# bcdwatch.net
KiCad netlist of a schematic drawn in EAGLE
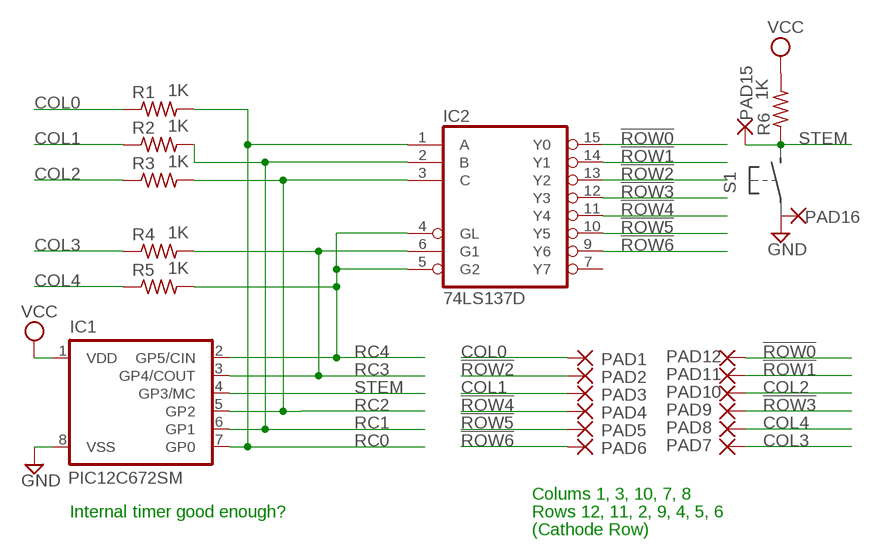
[diagram p0: schematic, sheet 1]

(export (version "E")
  (design (tool "Eeschema 10.0.6"))
  (components
    (comp (ref "IC1")
      (value "PIC12C672SM")
      (footprint "eagle-import:SO-08M")
      (fields (field (name "MF") "MICROCHIP") (field (name "MPN") "PIC12C672-04/SM"))
      (libsource (lib "eagle-import") (part "PIC12C?SM672"))
    )
    (comp (ref "IC2")
      (value "74LS137D")
      (footprint "eagle-import:SO16")
      (libsource (lib "eagle-import") (part "74137DLS"))
    )
    (comp (ref "PAD1")
      (value "SMD2")
      (footprint "eagle-import:SMD1,27-2,54")
      (libsource (lib "eagle-import") (part "SMD2"))
    )
    (comp (ref "PAD2")
      (value "SMD2")
      (footprint "eagle-import:SMD1,27-2,54")
      (libsource (lib "eagle-import") (part "SMD2"))
    )
    (comp (ref "PAD3")
      (value "SMD2")
      (footprint "eagle-import:SMD1,27-2,54")
      (libsource (lib "eagle-import") (part "SMD2"))
    )
    (comp (ref "PAD4")
      (value "SMD2")
      (footprint "eagle-import:SMD1,27-2,54")
      (libsource (lib "eagle-import") (part "SMD2"))
    )
    (comp (ref "PAD5")
      (value "SMD2")
      (footprint "eagle-import:SMD1,27-2,54")
      (libsource (lib "eagle-import") (part "SMD2"))
    )
    (comp (ref "PAD6")
      (value "SMD2")
      (footprint "eagle-import:SMD1,27-2,54")
      (libsource (lib "eagle-import") (part "SMD2"))
    )
    (comp (ref "PAD7")
      (value "SMD2")
      (footprint "eagle-import:SMD1,27-2,54")
      (libsource (lib "eagle-import") (part "SMD2"))
    )
    (comp (ref "PAD8")
      (value "SMD2")
      (footprint "eagle-import:SMD1,27-2,54")
      (libsource (lib "eagle-import") (part "SMD2"))
    )
    (comp (ref "PAD9")
      (value "SMD2")
      (footprint "eagle-import:SMD1,27-2,54")
      (libsource (lib "eagle-import") (part "SMD2"))
    )
    (comp (ref "PAD10")
      (value "SMD2")
      (footprint "eagle-import:SMD1,27-2,54")
      (libsource (lib "eagle-import") (part "SMD2"))
    )
    (comp (ref "PAD11")
      (value "SMD2")
      (footprint "eagle-import:SMD1,27-2,54")
      (libsource (lib "eagle-import") (part "SMD2"))
    )
    (comp (ref "PAD12")
      (value "SMD2")
      (footprint "eagle-import:SMD1,27-2,54")
      (libsource (lib "eagle-import") (part "SMD2"))
    )
    (comp (ref "PAD15")
      (value "SMD2")
      (footprint "eagle-import:SMD1,27-2,54")
      (libsource (lib "eagle-import") (part "SMD2"))
    )
    (comp (ref "PAD16")
      (value "SMD2")
      (footprint "eagle-import:SMD1,27-2,54")
      (libsource (lib "eagle-import") (part "SMD2"))
    )
    (comp (ref "R1")
      (value "1K")
      (footprint "eagle-import:R0805")
      (libsource (lib "eagle-import") (part "R-US_R0805"))
    )
    (comp (ref "R2")
      (value "1K")
      (footprint "eagle-import:R0805")
      (libsource (lib "eagle-import") (part "R-US_R0805"))
    )
    (comp (ref "R3")
      (value "1K")
      (footprint "eagle-import:R0805")
      (libsource (lib "eagle-import") (part "R-US_R0805"))
    )
    (comp (ref "R4")
      (value "1K")
      (footprint "eagle-import:R0805")
      (libsource (lib "eagle-import") (part "R-US_R0805"))
    )
    (comp (ref "R5")
      (value "1K")
      (footprint "eagle-import:R0805")
      (libsource (lib "eagle-import") (part "R-US_R0805"))
    )
    (comp (ref "R6")
      (value "1K")
      (footprint "eagle-import:R0805")
      (libsource (lib "eagle-import") (part "R-US_R0805"))
    )
  )
  (nets
    (net (code "1") (name "/COL0") (class "Default")
      (node (ref "PAD1") (pin "1") (pinfunction "P_1") (pintype "passive"))
      (node (ref "R1") (pin "1") (pinfunction "1_1") (pintype "passive"))
    )
    (net (code "2") (name "/COL1") (class "Default")
      (node (ref "PAD3") (pin "1") (pinfunction "P_1") (pintype "passive"))
      (node (ref "R2") (pin "1") (pinfunction "1_1") (pintype "passive"))
    )
    (net (code "3") (name "/COL2") (class "Default")
      (node (ref "PAD10") (pin "1") (pinfunction "P_1") (pintype "passive"))
      (node (ref "R3") (pin "1") (pinfunction "1_1") (pintype "passive"))
    )
    (net (code "4") (name "/COL3") (class "Default")
      (node (ref "PAD7") (pin "1") (pinfunction "P_1") (pintype "passive"))
      (node (ref "R4") (pin "1") (pinfunction "1_1") (pintype "passive"))
    )
    (net (code "5") (name "/COL4") (class "Default")
      (node (ref "PAD8") (pin "1") (pinfunction "P_1") (pintype "passive"))
      (node (ref "R5") (pin "1") (pinfunction "1_1") (pintype "passive"))
    )
    (net (code "6") (name "/RC0") (class "Default")
      (node (ref "IC1") (pin "7") (pinfunction "GP0_7") (pintype "bidirectional"))
      (node (ref "IC2") (pin "1") (pinfunction "A_1") (pintype "input"))
      (node (ref "R1") (pin "2") (pinfunction "2_2") (pintype "passive"))
    )
    (net (code "7") (name "/RC1") (class "Default")
      (node (ref "IC1") (pin "6") (pinfunction "GP1_6") (pintype "bidirectional"))
      (node (ref "IC2") (pin "2") (pinfunction "B_2") (pintype "input"))
      (node (ref "R2") (pin "2") (pinfunction "2_2") (pintype "passive"))
    )
    (net (code "8") (name "/RC2") (class "Default")
      (node (ref "IC1") (pin "5") (pinfunction "GP2_5") (pintype "bidirectional"))
      (node (ref "IC2") (pin "3") (pinfunction "C_3") (pintype "input"))
      (node (ref "R3") (pin "2") (pinfunction "2_2") (pintype "passive"))
    )
    (net (code "9") (name "/RC3") (class "Default")
      (node (ref "IC1") (pin "3") (pinfunction "GP4/COUT_3") (pintype "bidirectional"))
      (node (ref "IC2") (pin "6") (pinfunction "G1_6") (pintype "input"))
      (node (ref "R4") (pin "2") (pinfunction "2_2") (pintype "passive"))
    )
    (net (code "10") (name "/RC4") (class "Default")
      (node (ref "IC1") (pin "2") (pinfunction "GP5/CIN_2") (pintype "bidirectional"))
      (node (ref "IC2") (pin "4") (pinfunction "GL_4") (pintype "input"))
      (node (ref "IC2") (pin "5") (pinfunction "G2_5") (pintype "input"))
      (node (ref "R5") (pin "2") (pinfunction "2_2") (pintype "passive"))
    )
    (net (code "11") (name "/STEM") (class "Default")
      (node (ref "IC1") (pin "4") (pinfunction "GP3/MC_4") (pintype "input"))
      (node (ref "PAD15") (pin "1") (pinfunction "P_1") (pintype "passive"))
      (node (ref "R6") (pin "1") (pinfunction "1_1") (pintype "passive"))
    )
    (net (code "12") (name "/~{ROW0}") (class "Default")
      (node (ref "IC2") (pin "15") (pinfunction "Y0_15") (pintype "output"))
      (node (ref "PAD12") (pin "1") (pinfunction "P_1") (pintype "passive"))
    )
    (net (code "13") (name "/~{ROW1}") (class "Default")
      (node (ref "IC2") (pin "14") (pinfunction "Y1_14") (pintype "output"))
      (node (ref "PAD11") (pin "1") (pinfunction "P_1") (pintype "passive"))
    )
    (net (code "14") (name "/~{ROW2}") (class "Default")
      (node (ref "IC2") (pin "13") (pinfunction "Y2_13") (pintype "output"))
      (node (ref "PAD2") (pin "1") (pinfunction "P_1") (pintype "passive"))
    )
    (net (code "15") (name "/~{ROW3}") (class "Default")
      (node (ref "IC2") (pin "12") (pinfunction "Y3_12") (pintype "output"))
      (node (ref "PAD9") (pin "1") (pinfunction "P_1") (pintype "passive"))
    )
    (net (code "16") (name "/~{ROW4}") (class "Default")
      (node (ref "IC2") (pin "11") (pinfunction "Y4_11") (pintype "output"))
      (node (ref "PAD4") (pin "1") (pinfunction "P_1") (pintype "passive"))
    )
    (net (code "17") (name "/~{ROW5}") (class "Default")
      (node (ref "IC2") (pin "10") (pinfunction "Y5_10") (pintype "output"))
      (node (ref "PAD5") (pin "1") (pinfunction "P_1") (pintype "passive"))
    )
    (net (code "18") (name "/~{ROW6}") (class "Default")
      (node (ref "IC2") (pin "9") (pinfunction "Y6_9") (pintype "output"))
      (node (ref "PAD6") (pin "1") (pinfunction "P_1") (pintype "passive"))
    )
    (net (code "19") (name "GND") (class "Default")
      (node (ref "IC1") (pin "8") (pinfunction "VSS_8") (pintype "power_in"))
      (node (ref "PAD16") (pin "1") (pinfunction "P_1") (pintype "passive"))
    )
    (net (code "20") (name "VCC") (class "Default")
      (node (ref "IC1") (pin "1") (pinfunction "VDD_1") (pintype "power_in"))
      (node (ref "R6") (pin "2") (pinfunction "2_2") (pintype "passive"))
    )
    (net (code "21") (name "unconnected-(IC2A-Y7-Pad7)") (class "Default")
      (node (ref "IC2") (pin "7") (pinfunction "Y7_7") (pintype "output"))
    )
  )
)
